# 02b3_USB_UART_BRIDGE.net
KiCad netlist of a schematic drawn in Altium Designer
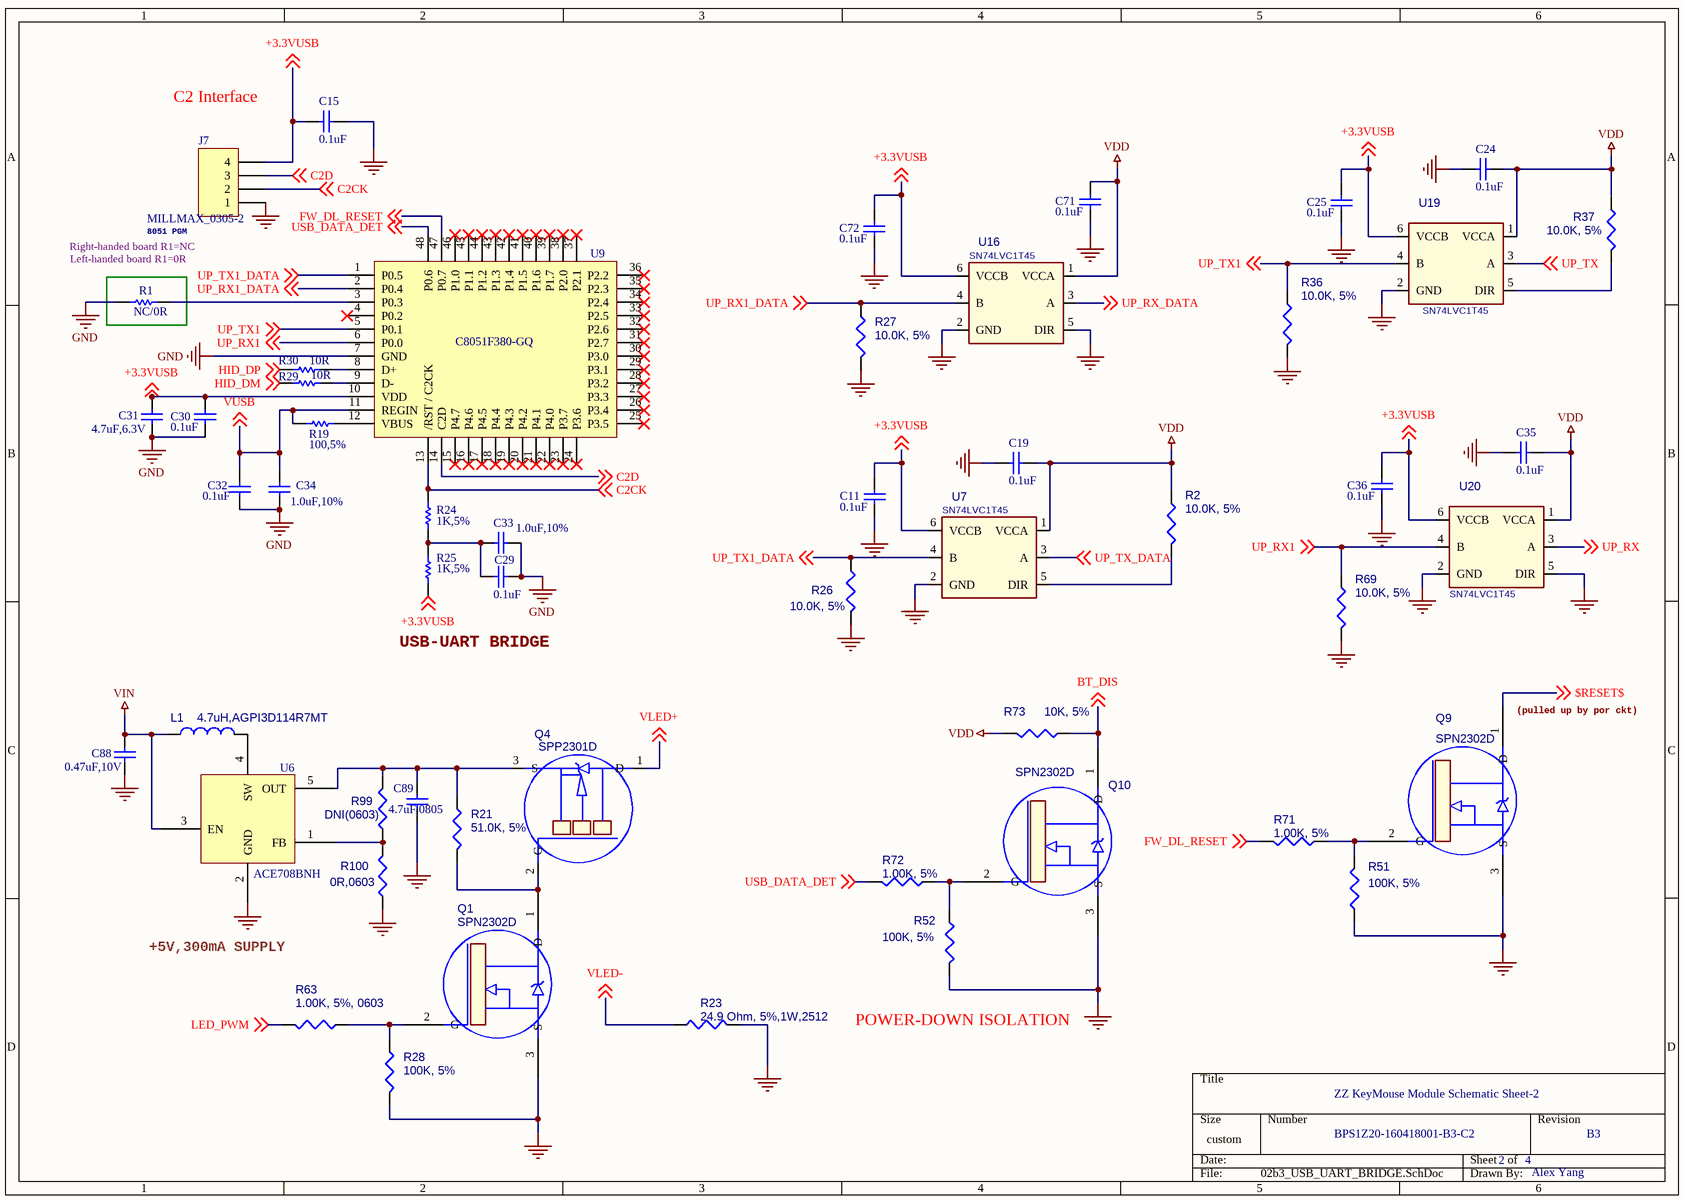
[diagram p0: 02b3_USB_UART_BRIDGE.SchDoc]

(export (version "E")
  (design (tool "Eeschema 10.0.6"))
  (components
    (comp (ref "C11")
      (value "0.1uF")
      (footprint "0603")
      (description "Capacitor")
      (libsource (lib "Miscellaneous Devices") (part "Cap"))
    )
    (comp (ref "C15")
      (value "0.1uF")
      (footprint "0603")
      (description "Capacitor")
      (libsource (lib "Miscellaneous Devices") (part "Cap"))
    )
    (comp (ref "C19")
      (value "0.1uF")
      (footprint "0603")
      (description "Capacitor")
      (libsource (lib "Miscellaneous Devices") (part "Cap"))
    )
    (comp (ref "C24")
      (value "0.1uF")
      (footprint "0603")
      (description "Capacitor")
      (libsource (lib "Miscellaneous Devices") (part "Cap"))
    )
    (comp (ref "C25")
      (value "0.1uF")
      (footprint "0603")
      (description "Capacitor")
      (libsource (lib "Miscellaneous Devices") (part "Cap"))
    )
    (comp (ref "C29")
      (value "0.1uF")
      (footprint "0603")
      (description "Capacitor")
      (libsource (lib "Miscellaneous Devices") (part "Cap"))
    )
    (comp (ref "C30")
      (value "0.1uF")
      (footprint "0603")
      (description "Capacitor")
      (libsource (lib "Miscellaneous Devices") (part "Cap"))
    )
    (comp (ref "C31")
      (value "4.7uF,6.3V")
      (footprint "0603")
      (description "Capacitor")
      (libsource (lib "Miscellaneous Devices") (part "Cap"))
    )
    (comp (ref "C32")
      (value "0.1uF")
      (footprint "0603")
      (description "Capacitor")
      (libsource (lib "Miscellaneous Devices") (part "Cap"))
    )
    (comp (ref "C33")
      (value "1.0uF,10%")
      (footprint "0603")
      (description "Capacitor")
      (libsource (lib "Miscellaneous Devices") (part "Cap"))
    )
    (comp (ref "C34")
      (value "1.0uF,10%")
      (footprint "0603")
      (description "Capacitor")
      (libsource (lib "Miscellaneous Devices") (part "Cap"))
    )
    (comp (ref "C35")
      (value "0.1uF")
      (footprint "0603")
      (description "Capacitor")
      (libsource (lib "Miscellaneous Devices") (part "Cap"))
    )
    (comp (ref "C36")
      (value "0.1uF")
      (footprint "0603")
      (description "Capacitor")
      (libsource (lib "Miscellaneous Devices") (part "Cap"))
    )
    (comp (ref "C71")
      (value "0.1uF")
      (footprint "0603")
      (description "Capacitor")
      (libsource (lib "Miscellaneous Devices") (part "Cap"))
    )
    (comp (ref "C72")
      (value "0.1uF")
      (footprint "0603")
      (description "Capacitor")
      (libsource (lib "Miscellaneous Devices") (part "Cap"))
    )
    (comp (ref "C88")
      (value "0.47uF,10V")
      (footprint "0603")
      (description "Capacitor")
      (libsource (lib "Miscellaneous Devices") (part "Cap"))
    )
    (comp (ref "C89")
      (value "4.7uF,0805")
      (footprint "0805")
      (description "Capacitor")
      (libsource (lib "Miscellaneous Devices") (part "Cap"))
    )
    (comp (ref "J7")
      (value "MILLMAX_0305-2")
      (footprint "MILLMAX_0305-2_4-POS")
      (description "Header, 4-Pin")
      (fields (field (name "PUBLISHER") "Altium Limited"))
      (libsource (lib "Miscellaneous Connectors") (part "Header 4"))
    )
    (comp (ref "L1")
      (value "4.7uH,AGPI3D114R7MT")
      (footprint "AGPI13D114R7MT")
      (libsource (lib "*") (part "INDUCTOR"))
    )
    (comp (ref "Q1") (value "SPN2302D") (footprint "SOT23") (libsource (lib "L MAIN") (part "AO3416")))
    (comp (ref "Q4") (value "SPP2301D") (footprint "SOT23") (libsource (lib "R MAIN") (part "AO3435")))
    (comp (ref "Q9") (value "SPN2302D") (footprint "SOT23") (libsource (lib "L MAIN") (part "AO3416")))
    (comp (ref "Q10") (value "SPN2302D") (footprint "SOT23") (libsource (lib "L MAIN") (part "AO3416")))
    (comp (ref "R1")
      (value "NC/0R")
      (footprint "0402")
      (description "Resistor")
      (fields (field (name "PUBLISHER") "Altium Limited"))
      (libsource (lib "Miscellaneous Devices") (part "Res1"))
    )
    (comp (ref "R2") (value "10.0K, 5%") (footprint "0402") (libsource (lib "*") (part "R")))
    (comp (ref "R19")
      (value "100,5%")
      (footprint "0402")
      (description "Resistor")
      (fields (field (name "PUBLISHER") "Altium Limited"))
      (libsource (lib "Miscellaneous Devices") (part "Res1"))
    )
    (comp (ref "R21") (value "51.0K, 5%") (footprint "0402") (libsource (lib "*") (part "R")))
    (comp (ref "R23")
      (value "24.9 Ohm, 5%,1W,2512")
      (footprint "RESC6432X70")
      (libsource (lib "*") (part "R"))
    )
    (comp (ref "R24")
      (value "1K,5%")
      (footprint "0402")
      (description "Resistor")
      (fields (field (name "PUBLISHER") "Altium Limited"))
      (libsource (lib "Miscellaneous Devices") (part "Res1"))
    )
    (comp (ref "R25")
      (value "1K,5%")
      (footprint "0402")
      (description "Resistor")
      (fields (field (name "PUBLISHER") "Altium Limited"))
      (libsource (lib "Miscellaneous Devices") (part "Res1"))
    )
    (comp (ref "R26") (value "10.0K, 5%") (footprint "0402") (libsource (lib "*") (part "R")))
    (comp (ref "R27") (value "10.0K, 5%") (footprint "0402") (libsource (lib "*") (part "R")))
    (comp (ref "R28") (value "100K, 5%") (footprint "0402") (libsource (lib "*") (part "R")))
    (comp (ref "R29")
      (value "10R")
      (footprint "0402")
      (description "Resistor")
      (fields (field (name "PUBLISHER") "Altium Limited"))
      (libsource (lib "Miscellaneous Devices") (part "Res1"))
    )
    (comp (ref "R30")
      (value "10R")
      (footprint "0402")
      (description "Resistor")
      (fields (field (name "PUBLISHER") "Altium Limited"))
      (libsource (lib "Miscellaneous Devices") (part "Res1"))
    )
    (comp (ref "R36") (value "10.0K, 5%") (footprint "0402") (libsource (lib "*") (part "R")))
    (comp (ref "R37") (value "10.0K, 5%") (footprint "0402") (libsource (lib "*") (part "R")))
    (comp (ref "R51") (value "100K, 5%") (footprint "0402") (libsource (lib "*") (part "R")))
    (comp (ref "R52") (value "100K, 5%") (footprint "0402") (libsource (lib "*") (part "R")))
    (comp (ref "R63") (value "1.00K, 5%, 0603") (footprint "0402") (libsource (lib "*") (part "R")))
    (comp (ref "R69") (value "10.0K, 5%") (footprint "0402") (libsource (lib "*") (part "R")))
    (comp (ref "R71") (value "1.00K, 5%") (footprint "0402") (libsource (lib "*") (part "R")))
    (comp (ref "R72") (value "1.00K, 5%") (footprint "0402") (libsource (lib "*") (part "R")))
    (comp (ref "R73") (value "10K, 5%") (footprint "0402") (libsource (lib "*") (part "R")))
    (comp (ref "R99") (value "DNI(0603)") (footprint "0402") (libsource (lib "*") (part "R")))
    (comp (ref "R100") (value "0R,0603") (footprint "0402") (libsource (lib "*") (part "R")))
    (comp (ref "U6")
      (value "ACE708BNH")
      (footprint "SOT23-5")
      (fields (field (name "PUBLISHER") "Altium Limited"))
      (libsource (lib "ZZ KeyMouse Module") (part "ACE708BNH"))
    )
    (comp (ref "U7") (value "SN74LVC1T45") (footprint "SOT23-6") (libsource (lib "*") (part "SN74LVC1T45")))
    (comp (ref "U9")
      (value "C8051F380-GQ")
      (footprint "TQFP48")
      (libsource (lib "C8051F380-GQ") (part "C8051F380-GQ"))
    )
    (comp (ref "U16") (value "SN74LVC1T45") (footprint "SOT23-6") (libsource (lib "*") (part "SN74LVC1T45")))
    (comp (ref "U19") (value "SN74LVC1T45") (footprint "SOT23-6") (libsource (lib "*") (part "SN74LVC1T45")))
    (comp (ref "U20") (value "SN74LVC1T45") (footprint "SOT23-6") (libsource (lib "*") (part "SN74LVC1T45")))
  )
  (nets
    (net (code "1") (name "$RESET$") (class "Default")
      (node (ref "Q9") (pin "1") (pinfunction "D_1") (pintype "passive"))
    )
    (net (code "2") (name "+3.3VUSB") (class "Default")
      (node (ref "C11") (pin "1") (pinfunction "1_1") (pintype "passive"))
      (node (ref "C15") (pin "2") (pinfunction "2_2") (pintype "passive"))
      (node (ref "C25") (pin "1") (pinfunction "1_1") (pintype "passive"))
      (node (ref "C30") (pin "1") (pinfunction "1_1") (pintype "passive"))
      (node (ref "C31") (pin "2") (pinfunction "2_2") (pintype "passive"))
      (node (ref "C36") (pin "1") (pinfunction "1_1") (pintype "passive"))
      (node (ref "C72") (pin "1") (pinfunction "1_1") (pintype "passive"))
      (node (ref "J7") (pin "4") (pinfunction "4_4") (pintype "passive"))
      (node (ref "R25") (pin "1") (pinfunction "1_1") (pintype "passive"))
      (node (ref "U16") (pin "6") (pinfunction "VCCB_6") (pintype "power_in"))
      (node (ref "U19") (pin "6") (pinfunction "VCCB_6") (pintype "power_in"))
      (node (ref "U20") (pin "6") (pinfunction "VCCB_6") (pintype "power_in"))
      (node (ref "U7") (pin "6") (pinfunction "VCCB_6") (pintype "power_in"))
      (node (ref "U9") (pin "10") (pinfunction "VDD_10") (pintype "power_in"))
    )
    (net (code "3") (name "BT_DIS") (class "Default")
      (node (ref "Q10") (pin "1") (pinfunction "D_1") (pintype "passive"))
      (node (ref "R73") (pin "2") (pinfunction "2_2") (pintype "passive"))
    )
    (net (code "4") (name "C2CK") (class "Default")
      (node (ref "J7") (pin "2") (pinfunction "2_2") (pintype "passive"))
      (node (ref "R24") (pin "2") (pinfunction "2_2") (pintype "passive"))
      (node (ref "U9") (pin "13") (pinfunction "/RST_/_C2CK_13") (pintype "power_in"))
    )
    (net (code "5") (name "C2D") (class "Default")
      (node (ref "J7") (pin "3") (pinfunction "3_3") (pintype "passive"))
      (node (ref "U9") (pin "14") (pinfunction "C2D_14") (pintype "power_in"))
    )
    (net (code "6") (name "FW_DL_RESET") (class "Default")
      (node (ref "R71") (pin "1") (pinfunction "1_1") (pintype "passive"))
      (node (ref "U9") (pin "47") (pinfunction "P0.7_47") (pintype "power_in"))
    )
    (net (code "7") (name "GND") (class "Default")
      (node (ref "C11") (pin "2") (pinfunction "2_2") (pintype "passive"))
      (node (ref "C15") (pin "1") (pinfunction "1_1") (pintype "passive"))
      (node (ref "C19") (pin "1") (pinfunction "1_1") (pintype "passive"))
      (node (ref "C24") (pin "1") (pinfunction "1_1") (pintype "passive"))
      (node (ref "C25") (pin "2") (pinfunction "2_2") (pintype "passive"))
      (node (ref "C29") (pin "1") (pinfunction "1_1") (pintype "passive"))
      (node (ref "C30") (pin "2") (pinfunction "2_2") (pintype "passive"))
      (node (ref "C31") (pin "1") (pinfunction "1_1") (pintype "passive"))
      (node (ref "C32") (pin "2") (pinfunction "2_2") (pintype "passive"))
      (node (ref "C33") (pin "1") (pinfunction "1_1") (pintype "passive"))
      (node (ref "C34") (pin "1") (pinfunction "1_1") (pintype "passive"))
      (node (ref "C35") (pin "1") (pinfunction "1_1") (pintype "passive"))
      (node (ref "C36") (pin "2") (pinfunction "2_2") (pintype "passive"))
      (node (ref "C71") (pin "2") (pinfunction "2_2") (pintype "passive"))
      (node (ref "C72") (pin "2") (pinfunction "2_2") (pintype "passive"))
      (node (ref "C88") (pin "1") (pinfunction "1_1") (pintype "passive"))
      (node (ref "C89") (pin "1") (pinfunction "1_1") (pintype "passive"))
      (node (ref "J7") (pin "1") (pinfunction "1_1") (pintype "passive"))
      (node (ref "Q1") (pin "3") (pinfunction "S_3") (pintype "passive"))
      (node (ref "Q10") (pin "3") (pinfunction "S_3") (pintype "passive"))
      (node (ref "Q9") (pin "3") (pinfunction "S_3") (pintype "passive"))
      (node (ref "R1") (pin "1") (pinfunction "1_1") (pintype "passive"))
      (node (ref "R100") (pin "2") (pinfunction "2_2") (pintype "passive"))
      (node (ref "R23") (pin "2") (pinfunction "2_2") (pintype "passive"))
      (node (ref "R26") (pin "2") (pinfunction "2_2") (pintype "passive"))
      (node (ref "R27") (pin "2") (pinfunction "2_2") (pintype "passive"))
      (node (ref "R28") (pin "1") (pinfunction "1_1") (pintype "passive"))
      (node (ref "R36") (pin "2") (pinfunction "2_2") (pintype "passive"))
      (node (ref "R51") (pin "1") (pinfunction "1_1") (pintype "passive"))
      (node (ref "R52") (pin "1") (pinfunction "1_1") (pintype "passive"))
      (node (ref "R69") (pin "2") (pinfunction "2_2") (pintype "passive"))
      (node (ref "U16") (pin "2") (pinfunction "GND_2") (pintype "passive"))
      (node (ref "U16") (pin "5") (pinfunction "DIR_5") (pintype "passive"))
      (node (ref "U19") (pin "2") (pinfunction "GND_2") (pintype "passive"))
      (node (ref "U20") (pin "2") (pinfunction "GND_2") (pintype "passive"))
      (node (ref "U20") (pin "5") (pinfunction "DIR_5") (pintype "passive"))
      (node (ref "U6") (pin "2") (pinfunction "GND_2") (pintype "passive"))
      (node (ref "U7") (pin "2") (pinfunction "GND_2") (pintype "passive"))
      (node (ref "U9") (pin "7") (pinfunction "GND_7") (pintype "passive"))
    )
    (net (code "8") (name "HID_DM") (class "Default")
      (node (ref "R29") (pin "1") (pinfunction "1_1") (pintype "passive"))
    )
    (net (code "9") (name "HID_DP") (class "Default")
      (node (ref "R30") (pin "1") (pinfunction "1_1") (pintype "passive"))
    )
    (net (code "10") (name "LED_PWM") (class "Default")
      (node (ref "R63") (pin "1") (pinfunction "1_1") (pintype "passive"))
    )
    (net (code "11") (name "Net-(C29-Pad2)") (class "Default")
      (node (ref "C29") (pin "2") (pinfunction "2_2") (pintype "passive"))
      (node (ref "C33") (pin "2") (pinfunction "2_2") (pintype "passive"))
      (node (ref "R24") (pin "1") (pinfunction "1_1") (pintype "passive"))
      (node (ref "R25") (pin "2") (pinfunction "2_2") (pintype "passive"))
    )
    (net (code "12") (name "Net-(Q1-D)") (class "Default")
      (node (ref "Q1") (pin "1") (pinfunction "D_1") (pintype "passive"))
      (node (ref "Q4") (pin "2") (pinfunction "G_2") (pintype "passive"))
      (node (ref "R21") (pin "2") (pinfunction "2_2") (pintype "passive"))
    )
    (net (code "13") (name "Net-(Q1-G)") (class "Default")
      (node (ref "Q1") (pin "2") (pinfunction "G_2") (pintype "passive"))
      (node (ref "R28") (pin "2") (pinfunction "2_2") (pintype "passive"))
      (node (ref "R63") (pin "2") (pinfunction "2_2") (pintype "passive"))
    )
    (net (code "14") (name "Net-(Q4-S)") (class "Default")
      (node (ref "C89") (pin "2") (pinfunction "2_2") (pintype "passive"))
      (node (ref "Q4") (pin "3") (pinfunction "S_3") (pintype "passive"))
      (node (ref "R21") (pin "1") (pinfunction "1_1") (pintype "passive"))
      (node (ref "R99") (pin "1") (pinfunction "1_1") (pintype "passive"))
      (node (ref "U6") (pin "5") (pinfunction "OUT_5") (pintype "passive"))
    )
    (net (code "15") (name "Net-(Q9-G)") (class "Default")
      (node (ref "Q9") (pin "2") (pinfunction "G_2") (pintype "passive"))
      (node (ref "R51") (pin "2") (pinfunction "2_2") (pintype "passive"))
      (node (ref "R71") (pin "2") (pinfunction "2_2") (pintype "passive"))
    )
    (net (code "16") (name "Net-(Q10-G)") (class "Default")
      (node (ref "Q10") (pin "2") (pinfunction "G_2") (pintype "passive"))
      (node (ref "R52") (pin "2") (pinfunction "2_2") (pintype "passive"))
      (node (ref "R72") (pin "2") (pinfunction "2_2") (pintype "passive"))
    )
    (net (code "17") (name "Net-(U6-FB)") (class "Default")
      (node (ref "R100") (pin "1") (pinfunction "1_1") (pintype "passive"))
      (node (ref "R99") (pin "2") (pinfunction "2_2") (pintype "passive"))
      (node (ref "U6") (pin "1") (pinfunction "FB_1") (pintype "passive"))
    )
    (net (code "18") (name "Net-(U6-SW)") (class "Default")
      (node (ref "L1") (pin "2") (pinfunction "2_2") (pintype "passive"))
      (node (ref "U6") (pin "4") (pinfunction "SW_4") (pintype "passive"))
    )
    (net (code "19") (name "Net-(U7-DIR)") (class "Default")
      (node (ref "R2") (pin "2") (pinfunction "2_2") (pintype "passive"))
      (node (ref "U7") (pin "5") (pinfunction "DIR_5") (pintype "passive"))
    )
    (net (code "20") (name "Net-(U9-D+)") (class "Default")
      (node (ref "R30") (pin "2") (pinfunction "2_2") (pintype "passive"))
      (node (ref "U9") (pin "8") (pinfunction "D+_8") (pintype "passive"))
    )
    (net (code "21") (name "Net-(U9-D-)") (class "Default")
      (node (ref "R29") (pin "2") (pinfunction "2_2") (pintype "passive"))
      (node (ref "U9") (pin "9") (pinfunction "D-_9") (pintype "power_in"))
    )
    (net (code "22") (name "Net-(U9-P0.3)") (class "Default")
      (node (ref "R1") (pin "2") (pinfunction "2_2") (pintype "passive"))
      (node (ref "U9") (pin "3") (pinfunction "P0.3_3") (pintype "power_in"))
    )
    (net (code "23") (name "Net-(U9-VBUS)") (class "Default")
      (node (ref "R19") (pin "2") (pinfunction "2_2") (pintype "passive"))
      (node (ref "U9") (pin "12") (pinfunction "VBUS_12") (pintype "passive"))
    )
    (net (code "24") (name "Net-(U19-DIR)") (class "Default")
      (node (ref "R37") (pin "2") (pinfunction "2_2") (pintype "passive"))
      (node (ref "U19") (pin "5") (pinfunction "DIR_5") (pintype "passive"))
    )
    (net (code "25") (name "UP_RX") (class "Default")
      (node (ref "U20") (pin "3") (pinfunction "A_3") (pintype "passive"))
    )
    (net (code "26") (name "UP_RX1") (class "Default")
      (node (ref "R69") (pin "1") (pinfunction "1_1") (pintype "passive"))
      (node (ref "U20") (pin "4") (pinfunction "B_4") (pintype "passive"))
      (node (ref "U9") (pin "6") (pinfunction "P0.0_6") (pintype "power_in"))
    )
    (net (code "27") (name "UP_RX1_DATA") (class "Default")
      (node (ref "R27") (pin "1") (pinfunction "1_1") (pintype "passive"))
      (node (ref "U16") (pin "4") (pinfunction "B_4") (pintype "passive"))
      (node (ref "U9") (pin "2") (pinfunction "P0.4_2") (pintype "power_in"))
    )
    (net (code "28") (name "UP_RX_DATA") (class "Default")
      (node (ref "U16") (pin "3") (pinfunction "A_3") (pintype "passive"))
    )
    (net (code "29") (name "UP_TX") (class "Default")
      (node (ref "U19") (pin "3") (pinfunction "A_3") (pintype "passive"))
    )
    (net (code "30") (name "UP_TX1") (class "Default")
      (node (ref "R36") (pin "1") (pinfunction "1_1") (pintype "passive"))
      (node (ref "U19") (pin "4") (pinfunction "B_4") (pintype "passive"))
      (node (ref "U9") (pin "5") (pinfunction "P0.1_5") (pintype "power_in"))
    )
    (net (code "31") (name "UP_TX1_DATA") (class "Default")
      (node (ref "R26") (pin "1") (pinfunction "1_1") (pintype "passive"))
      (node (ref "U7") (pin "4") (pinfunction "B_4") (pintype "passive"))
      (node (ref "U9") (pin "1") (pinfunction "P0.5_1") (pintype "passive"))
    )
    (net (code "32") (name "UP_TX_DATA") (class "Default")
      (node (ref "U7") (pin "3") (pinfunction "A_3") (pintype "passive"))
    )
    (net (code "33") (name "USB_DATA_DET") (class "Default")
      (node (ref "R72") (pin "1") (pinfunction "1_1") (pintype "passive"))
      (node (ref "U9") (pin "48") (pinfunction "P0.6_48") (pintype "power_in"))
    )
    (net (code "34") (name "VDD") (class "Default")
      (node (ref "C19") (pin "2") (pinfunction "2_2") (pintype "passive"))
      (node (ref "C24") (pin "2") (pinfunction "2_2") (pintype "passive"))
      (node (ref "C35") (pin "2") (pinfunction "2_2") (pintype "passive"))
      (node (ref "C71") (pin "1") (pinfunction "1_1") (pintype "passive"))
      (node (ref "R2") (pin "1") (pinfunction "1_1") (pintype "passive"))
      (node (ref "R37") (pin "1") (pinfunction "1_1") (pintype "passive"))
      (node (ref "R73") (pin "1") (pinfunction "1_1") (pintype "passive"))
      (node (ref "U16") (pin "1") (pinfunction "VCCA_1") (pintype "power_in"))
      (node (ref "U19") (pin "1") (pinfunction "VCCA_1") (pintype "power_in"))
      (node (ref "U20") (pin "1") (pinfunction "VCCA_1") (pintype "power_in"))
      (node (ref "U7") (pin "1") (pinfunction "VCCA_1") (pintype "power_in"))
    )
    (net (code "35") (name "VIN") (class "Default")
      (node (ref "C88") (pin "2") (pinfunction "2_2") (pintype "passive"))
      (node (ref "L1") (pin "1") (pinfunction "1_1") (pintype "passive"))
      (node (ref "U6") (pin "3") (pinfunction "EN_3") (pintype "passive"))
    )
    (net (code "36") (name "VLED+") (class "Default")
      (node (ref "Q4") (pin "1") (pinfunction "D_1") (pintype "passive"))
    )
    (net (code "37") (name "VLED-") (class "Default")
      (node (ref "R23") (pin "1") (pinfunction "1_1") (pintype "passive"))
    )
    (net (code "38") (name "VUSB") (class "Default")
      (node (ref "C32") (pin "1") (pinfunction "1_1") (pintype "passive"))
      (node (ref "C34") (pin "2") (pinfunction "2_2") (pintype "passive"))
      (node (ref "R19") (pin "1") (pinfunction "1_1") (pintype "passive"))
      (node (ref "U9") (pin "11") (pinfunction "REGIN_11") (pintype "passive"))
    )
    (net (code "39") (name "unconnected-(U9-P0.2-Pad4)") (class "Default")
      (node (ref "U9") (pin "4") (pinfunction "P0.2_4") (pintype "power_in+no_connect"))
    )
    (net (code "40") (name "unconnected-(U9-P1.0-Pad46)") (class "Default")
      (node (ref "U9") (pin "46") (pinfunction "P1.0_46") (pintype "power_in+no_connect"))
    )
    (net (code "41") (name "unconnected-(U9-P1.1-Pad45)") (class "Default")
      (node (ref "U9") (pin "45") (pinfunction "P1.1_45") (pintype "passive+no_connect"))
    )
    (net (code "42") (name "unconnected-(U9-P1.2-Pad44)") (class "Default")
      (node (ref "U9") (pin "44") (pinfunction "P1.2_44") (pintype "passive+no_connect"))
    )
    (net (code "43") (name "unconnected-(U9-P1.3-Pad43)") (class "Default")
      (node (ref "U9") (pin "43") (pinfunction "P1.3_43") (pintype "passive+no_connect"))
    )
    (net (code "44") (name "unconnected-(U9-P1.4-Pad42)") (class "Default")
      (node (ref "U9") (pin "42") (pinfunction "P1.4_42") (pintype "passive+no_connect"))
    )
    (net (code "45") (name "unconnected-(U9-P1.5-Pad41)") (class "Default")
      (node (ref "U9") (pin "41") (pinfunction "P1.5_41") (pintype "passive+no_connect"))
    )
    (net (code "46") (name "unconnected-(U9-P1.6-Pad40)") (class "Default")
      (node (ref "U9") (pin "40") (pinfunction "P1.6_40") (pintype "passive+no_connect"))
    )
    (net (code "47") (name "unconnected-(U9-P1.7-Pad39)") (class "Default")
      (node (ref "U9") (pin "39") (pinfunction "P1.7_39") (pintype "passive+no_connect"))
    )
    (net (code "48") (name "unconnected-(U9-P2.0-Pad38)") (class "Default")
      (node (ref "U9") (pin "38") (pinfunction "P2.0_38") (pintype "passive+no_connect"))
    )
    (net (code "49") (name "unconnected-(U9-P2.1-Pad37)") (class "Default")
      (node (ref "U9") (pin "37") (pinfunction "P2.1_37") (pintype "passive+no_connect"))
    )
    (net (code "50") (name "unconnected-(U9-P2.2-Pad36)") (class "Default")
      (node (ref "U9") (pin "36") (pinfunction "P2.2_36") (pintype "passive+no_connect"))
    )
    (net (code "51") (name "unconnected-(U9-P2.3-Pad35)") (class "Default")
      (node (ref "U9") (pin "35") (pinfunction "P2.3_35") (pintype "power_in+no_connect"))
    )
    (net (code "52") (name "unconnected-(U9-P2.4-Pad34)") (class "Default")
      (node (ref "U9") (pin "34") (pinfunction "P2.4_34") (pintype "power_in+no_connect"))
    )
    (net (code "53") (name "unconnected-(U9-P2.5-Pad33)") (class "Default")
      (node (ref "U9") (pin "33") (pinfunction "P2.5_33") (pintype "power_in+no_connect"))
    )
    (net (code "54") (name "unconnected-(U9-P2.6-Pad32)") (class "Default")
      (node (ref "U9") (pin "32") (pinfunction "P2.6_32") (pintype "power_in+no_connect"))
    )
    (net (code "55") (name "unconnected-(U9-P2.7-Pad31)") (class "Default")
      (node (ref "U9") (pin "31") (pinfunction "P2.7_31") (pintype "passive+no_connect"))
    )
    (net (code "56") (name "unconnected-(U9-P3.0-Pad30)") (class "Default")
      (node (ref "U9") (pin "30") (pinfunction "P3.0_30") (pintype "passive+no_connect"))
    )
    (net (code "57") (name "unconnected-(U9-P3.1-Pad29)") (class "Default")
      (node (ref "U9") (pin "29") (pinfunction "P3.1_29") (pintype "passive+no_connect"))
    )
    (net (code "58") (name "unconnected-(U9-P3.2-Pad28)") (class "Default")
      (node (ref "U9") (pin "28") (pinfunction "P3.2_28") (pintype "power_in+no_connect"))
    )
    (net (code "59") (name "unconnected-(U9-P3.3-Pad27)") (class "Default")
      (node (ref "U9") (pin "27") (pinfunction "P3.3_27") (pintype "passive+no_connect"))
    )
    (net (code "60") (name "unconnected-(U9-P3.4-Pad26)") (class "Default")
      (node (ref "U9") (pin "26") (pinfunction "P3.4_26") (pintype "passive+no_connect"))
    )
    (net (code "61") (name "unconnected-(U9-P3.5-Pad25)") (class "Default")
      (node (ref "U9") (pin "25") (pinfunction "P3.5_25") (pintype "passive+no_connect"))
    )
    (net (code "62") (name "unconnected-(U9-P3.6-Pad24)") (class "Default")
      (node (ref "U9") (pin "24") (pinfunction "P3.6_24") (pintype "passive+no_connect"))
    )
    (net (code "63") (name "unconnected-(U9-P3.7-Pad23)") (class "Default")
      (node (ref "U9") (pin "23") (pinfunction "P3.7_23") (pintype "passive+no_connect"))
    )
    (net (code "64") (name "unconnected-(U9-P4.0-Pad22)") (class "Default")
      (node (ref "U9") (pin "22") (pinfunction "P4.0_22") (pintype "passive+no_connect"))
    )
    (net (code "65") (name "unconnected-(U9-P4.1-Pad21)") (class "Default")
      (node (ref "U9") (pin "21") (pinfunction "P4.1_21") (pintype "passive+no_connect"))
    )
    (net (code "66") (name "unconnected-(U9-P4.2-Pad20)") (class "Default")
      (node (ref "U9") (pin "20") (pinfunction "P4.2_20") (pintype "passive+no_connect"))
    )
    (net (code "67") (name "unconnected-(U9-P4.3-Pad19)") (class "Default")
      (node (ref "U9") (pin "19") (pinfunction "P4.3_19") (pintype "passive+no_connect"))
    )
    (net (code "68") (name "unconnected-(U9-P4.4-Pad18)") (class "Default")
      (node (ref "U9") (pin "18") (pinfunction "P4.4_18") (pintype "passive+no_connect"))
    )
    (net (code "69") (name "unconnected-(U9-P4.5-Pad17)") (class "Default")
      (node (ref "U9") (pin "17") (pinfunction "P4.5_17") (pintype "passive+no_connect"))
    )
    (net (code "70") (name "unconnected-(U9-P4.6-Pad16)") (class "Default")
      (node (ref "U9") (pin "16") (pinfunction "P4.6_16") (pintype "passive+no_connect"))
    )
    (net (code "71") (name "unconnected-(U9-P4.7-Pad15)") (class "Default")
      (node (ref "U9") (pin "15") (pinfunction "P4.7_15") (pintype "power_in+no_connect"))
    )
  )
)
